# 4.net
KiCad netlist of a schematic drawn in Altium Designer
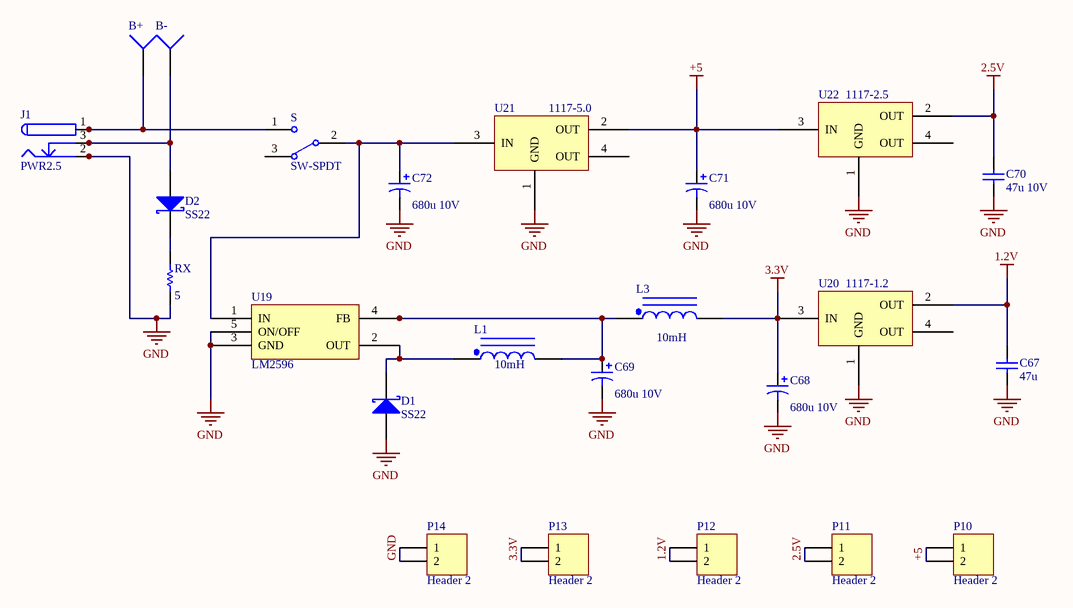
[diagram p0: 示波器原理图4.SchDoc]

(export (version "E")
  (design (tool "Eeschema 10.0.6"))
  (components
    (comp (ref "B+")
      (value "~")
      (footprint "PIN1")
      (description "Socket")
      (fields (field (name "PUBLISHER") "Altium Limited"))
      (libsource (lib "Miscellaneous Connectors") (part "Socket"))
    )
    (comp (ref "B-")
      (value "~")
      (footprint "PIN1")
      (description "Socket")
      (fields (field (name "PUBLISHER") "Altium Limited"))
      (libsource (lib "Miscellaneous Connectors") (part "Socket"))
    )
    (comp (ref "C67")
      (value "47u")
      (footprint "VP32-3.2")
      (description "Capacitor")
      (fields (field (name "PUBLISHER") "Altium Limited"))
      (libsource (lib "Miscellaneous Devices") (part "Cap"))
    )
    (comp (ref "C68")
      (value "680u 10V")
      (footprint "C0805")
      (description "Polarized Capacitor (Surface Mount)")
      (fields (field (name "PUBLISHER") "Altium Limited"))
      (libsource (lib "Miscellaneous Devices") (part "Cap Pol3"))
    )
    (comp (ref "C69")
      (value "680u 10V")
      (footprint "C0805")
      (description "Polarized Capacitor (Surface Mount)")
      (fields (field (name "PUBLISHER") "Altium Limited"))
      (libsource (lib "Miscellaneous Devices") (part "Cap Pol3"))
    )
    (comp (ref "C70")
      (value "47u 10V")
      (footprint "VP32-3.2")
      (description "Capacitor")
      (fields (field (name "PUBLISHER") "Altium Limited"))
      (libsource (lib "Miscellaneous Devices") (part "Cap"))
    )
    (comp (ref "C71")
      (value "680u 10V")
      (footprint "C0805")
      (description "Polarized Capacitor (Surface Mount)")
      (fields (field (name "PUBLISHER") "Altium Limited"))
      (libsource (lib "Miscellaneous Devices") (part "Cap Pol3"))
    )
    (comp (ref "C72")
      (value "680u 10V")
      (footprint "C0805")
      (description "Polarized Capacitor (Surface Mount)")
      (fields (field (name "PUBLISHER") "Altium Limited"))
      (libsource (lib "Miscellaneous Devices") (part "Cap Pol3"))
    )
    (comp (ref "D1")
      (value "SS22")
      (footprint "SMB")
      (description "Schottky Diode")
      (fields (field (name "PUBLISHER") "Altium Limited"))
      (libsource (lib "Miscellaneous Devices") (part "D Schottky"))
    )
    (comp (ref "D2")
      (value "SS22")
      (footprint "SMB")
      (description "Schottky Diode")
      (fields (field (name "PUBLISHER") "Altium Limited"))
      (libsource (lib "Miscellaneous Devices") (part "D Schottky"))
    )
    (comp (ref "J1")
      (value "PWR2.5")
      (footprint "KLD-0202")
      (description "Low Voltage Power Supply Connector")
      (fields (field (name "PUBLISHER") "Altium Limited"))
      (libsource (lib "Miscellaneous Connectors") (part "PWR2.5"))
    )
    (comp (ref "L1")
      (value "10mH")
      (footprint "DIODE_SMC")
      (description "Magnetic-Core Inductor with Winding Polarity Marking")
      (fields (field (name "PUBLISHER") "Altium Limited"))
      (libsource (lib "Miscellaneous Devices") (part "Inductor Iron Dot"))
    )
    (comp (ref "L3")
      (value "10mH")
      (footprint "DIODE_SMC")
      (description "Magnetic-Core Inductor with Winding Polarity Marking")
      (fields (field (name "PUBLISHER") "Altium Limited"))
      (libsource (lib "Miscellaneous Devices") (part "Inductor Iron Dot"))
    )
    (comp (ref "P10")
      (value "Header 2")
      (footprint "HDR1X2")
      (description "Header, 2-Pin")
      (fields (field (name "PUBLISHER") "Altium Limited"))
      (libsource (lib "Miscellaneous Connectors") (part "Header 2"))
    )
    (comp (ref "P11")
      (value "Header 2")
      (footprint "HDR1X2")
      (description "Header, 2-Pin")
      (fields (field (name "PUBLISHER") "Altium Limited"))
      (libsource (lib "Miscellaneous Connectors") (part "Header 2"))
    )
    (comp (ref "P12")
      (value "Header 2")
      (footprint "HDR1X2")
      (description "Header, 2-Pin")
      (fields (field (name "PUBLISHER") "Altium Limited"))
      (libsource (lib "Miscellaneous Connectors") (part "Header 2"))
    )
    (comp (ref "P13")
      (value "Header 2")
      (footprint "HDR1X2")
      (description "Header, 2-Pin")
      (fields (field (name "PUBLISHER") "Altium Limited"))
      (libsource (lib "Miscellaneous Connectors") (part "Header 2"))
    )
    (comp (ref "P14")
      (value "Header 2")
      (footprint "HDR1X2")
      (description "Header, 2-Pin")
      (fields (field (name "PUBLISHER") "Altium Limited"))
      (libsource (lib "Miscellaneous Connectors") (part "Header 2"))
    )
    (comp (ref "RX")
      (value "5")
      (footprint "AXIAL-0.3")
      (description "Resistor")
      (fields (field (name "PUBLISHER") "Altium Limited"))
      (libsource (lib "Miscellaneous Devices") (part "Res1"))
    )
    (comp (ref "S")
      (value "SW-SPDT")
      (footprint "TL36WW15050")
      (description "SPDT Subminiature Toggle Switch, Right Angle Mounting, Vertical Actuation")
      (fields (field (name "PUBLISHER") "Altium Limited"))
      (libsource (lib "Miscellaneous Devices") (part "SW-SPDT"))
    )
    (comp (ref "U19") (value "LM2596") (libsource (lib "LM2596S") (part "Component_1")))
    (comp (ref "U20")
      (value "1117-1.2")
      (footprint "Model Name")
      (libsource (lib "S1117-5V") (part "Component_1"))
    )
    (comp (ref "U21")
      (value "1117-5.0")
      (footprint "PCBComponent_1")
      (libsource (lib "S1117-5V") (part "Component_1"))
    )
    (comp (ref "U22")
      (value "1117-2.5")
      (footprint "PCBComponent_1")
      (libsource (lib "S1117-5V") (part "Component_1"))
    )
  )
  (nets
    (net (code "1") (name "+5") (class "Default")
      (node (ref "C71") (pin "1") (pinfunction "1_1") (pintype "passive"))
      (node (ref "P10") (pin "1") (pinfunction "1_1") (pintype "passive"))
      (node (ref "P10") (pin "2") (pinfunction "2_2") (pintype "passive"))
      (node (ref "U21") (pin "2") (pinfunction "OUT_2") (pintype "passive"))
      (node (ref "U22") (pin "3") (pinfunction "IN_3") (pintype "passive"))
    )
    (net (code "2") (name "1.2V") (class "Default")
      (node (ref "C67") (pin "1") (pinfunction "1_1") (pintype "passive"))
      (node (ref "P12") (pin "1") (pinfunction "1_1") (pintype "passive"))
      (node (ref "P12") (pin "2") (pinfunction "2_2") (pintype "passive"))
      (node (ref "U20") (pin "2") (pinfunction "OUT_2") (pintype "passive"))
    )
    (net (code "3") (name "2.5V") (class "Default")
      (node (ref "C70") (pin "1") (pinfunction "1_1") (pintype "passive"))
      (node (ref "P11") (pin "1") (pinfunction "1_1") (pintype "passive"))
      (node (ref "P11") (pin "2") (pinfunction "2_2") (pintype "passive"))
      (node (ref "U22") (pin "2") (pinfunction "OUT_2") (pintype "passive"))
    )
    (net (code "4") (name "3.3V") (class "Default")
      (node (ref "C68") (pin "1") (pinfunction "1_1") (pintype "passive"))
      (node (ref "L3") (pin "2") (pinfunction "2_2") (pintype "passive"))
      (node (ref "P13") (pin "1") (pinfunction "1_1") (pintype "passive"))
      (node (ref "P13") (pin "2") (pinfunction "2_2") (pintype "passive"))
      (node (ref "U20") (pin "3") (pinfunction "IN_3") (pintype "passive"))
    )
    (net (code "5") (name "GND") (class "Default")
      (node (ref "C67") (pin "2") (pinfunction "2_2") (pintype "passive"))
      (node (ref "C68") (pin "2") (pinfunction "2_2") (pintype "passive"))
      (node (ref "C69") (pin "2") (pinfunction "2_2") (pintype "passive"))
      (node (ref "C70") (pin "2") (pinfunction "2_2") (pintype "passive"))
      (node (ref "C71") (pin "2") (pinfunction "2_2") (pintype "passive"))
      (node (ref "C72") (pin "2") (pinfunction "2_2") (pintype "passive"))
      (node (ref "D1") (pin "1") (pinfunction "A_1") (pintype "passive"))
      (node (ref "J1") (pin "2") (pinfunction "2_2") (pintype "power_in"))
      (node (ref "J1") (pin "2A") (pinfunction "2A_2A") (pintype "power_in"))
      (node (ref "J1") (pin "2B") (pinfunction "2B_2B") (pintype "power_in"))
      (node (ref "P14") (pin "1") (pinfunction "1_1") (pintype "passive"))
      (node (ref "P14") (pin "2") (pinfunction "2_2") (pintype "passive"))
      (node (ref "RX") (pin "1") (pinfunction "1_1") (pintype "passive"))
      (node (ref "U19") (pin "3") (pinfunction "GND_3") (pintype "passive"))
      (node (ref "U19") (pin "5") (pinfunction "ON/OFF_5") (pintype "passive"))
      (node (ref "U20") (pin "1") (pinfunction "GND_1") (pintype "passive"))
      (node (ref "U21") (pin "1") (pinfunction "GND_1") (pintype "passive"))
      (node (ref "U22") (pin "1") (pinfunction "GND_1") (pintype "passive"))
    )
    (net (code "6") (name "Net-(B+-Pad1)") (class "Default")
      (node (ref "B+") (pin "1") (pinfunction "1_1") (pintype "passive"))
      (node (ref "J1") (pin "1") (pinfunction "1_1") (pintype "power_in"))
      (node (ref "J1") (pin "1A") (pinfunction "1A_1A") (pintype "power_in"))
      (node (ref "J1") (pin "1B") (pinfunction "1B_1B") (pintype "power_in"))
      (node (ref "S") (pin "1") (pinfunction "1_1") (pintype "passive"))
    )
    (net (code "7") (name "Net-(D1-K)") (class "Default")
      (node (ref "D1") (pin "2") (pinfunction "K_2") (pintype "passive"))
      (node (ref "L1") (pin "1") (pinfunction "1_1") (pintype "passive"))
      (node (ref "U19") (pin "2") (pinfunction "OUT_2") (pintype "passive"))
    )
    (net (code "8") (name "Net-(D2-A)") (class "Default")
      (node (ref "B-") (pin "1") (pinfunction "1_1") (pintype "passive"))
      (node (ref "D2") (pin "1") (pinfunction "A_1") (pintype "passive"))
      (node (ref "J1") (pin "3") (pinfunction "3_3") (pintype "power_in"))
      (node (ref "J1") (pin "3A") (pinfunction "3A_3A") (pintype "power_in"))
      (node (ref "J1") (pin "3B") (pinfunction "3B_3B") (pintype "power_in"))
    )
    (net (code "9") (name "Net-(D2-K)") (class "Default")
      (node (ref "D2") (pin "2") (pinfunction "K_2") (pintype "passive"))
      (node (ref "RX") (pin "2") (pinfunction "2_2") (pintype "passive"))
    )
    (net (code "10") (name "Net-(U19-FB)") (class "Default")
      (node (ref "C69") (pin "1") (pinfunction "1_1") (pintype "passive"))
      (node (ref "L1") (pin "2") (pinfunction "2_2") (pintype "passive"))
      (node (ref "L3") (pin "1") (pinfunction "1_1") (pintype "passive"))
      (node (ref "U19") (pin "4") (pinfunction "FB_4") (pintype "passive"))
    )
    (net (code "11") (name "Net-(U19-IN)") (class "Default")
      (node (ref "C72") (pin "1") (pinfunction "1_1") (pintype "passive"))
      (node (ref "S") (pin "2") (pinfunction "2_2") (pintype "passive"))
      (node (ref "U19") (pin "1") (pinfunction "IN_1") (pintype "passive"))
      (node (ref "U21") (pin "3") (pinfunction "IN_3") (pintype "passive"))
    )
    (net (code "12") (name "unconnected-(S-Pad3)") (class "Default")
      (node (ref "S") (pin "3") (pinfunction "3_3") (pintype "passive"))
    )
    (net (code "13") (name "unconnected-(U20-OUT-Pad4)") (class "Default")
      (node (ref "U20") (pin "4") (pinfunction "OUT_4") (pintype "passive"))
    )
    (net (code "14") (name "unconnected-(U21-OUT-Pad4)") (class "Default")
      (node (ref "U21") (pin "4") (pinfunction "OUT_4") (pintype "passive"))
    )
    (net (code "15") (name "unconnected-(U22-OUT-Pad4)") (class "Default")
      (node (ref "U22") (pin "4") (pinfunction "OUT_4") (pintype "passive"))
    )
  )
)
